# esp_v2.net
KiCad netlist of a schematic drawn in EAGLE
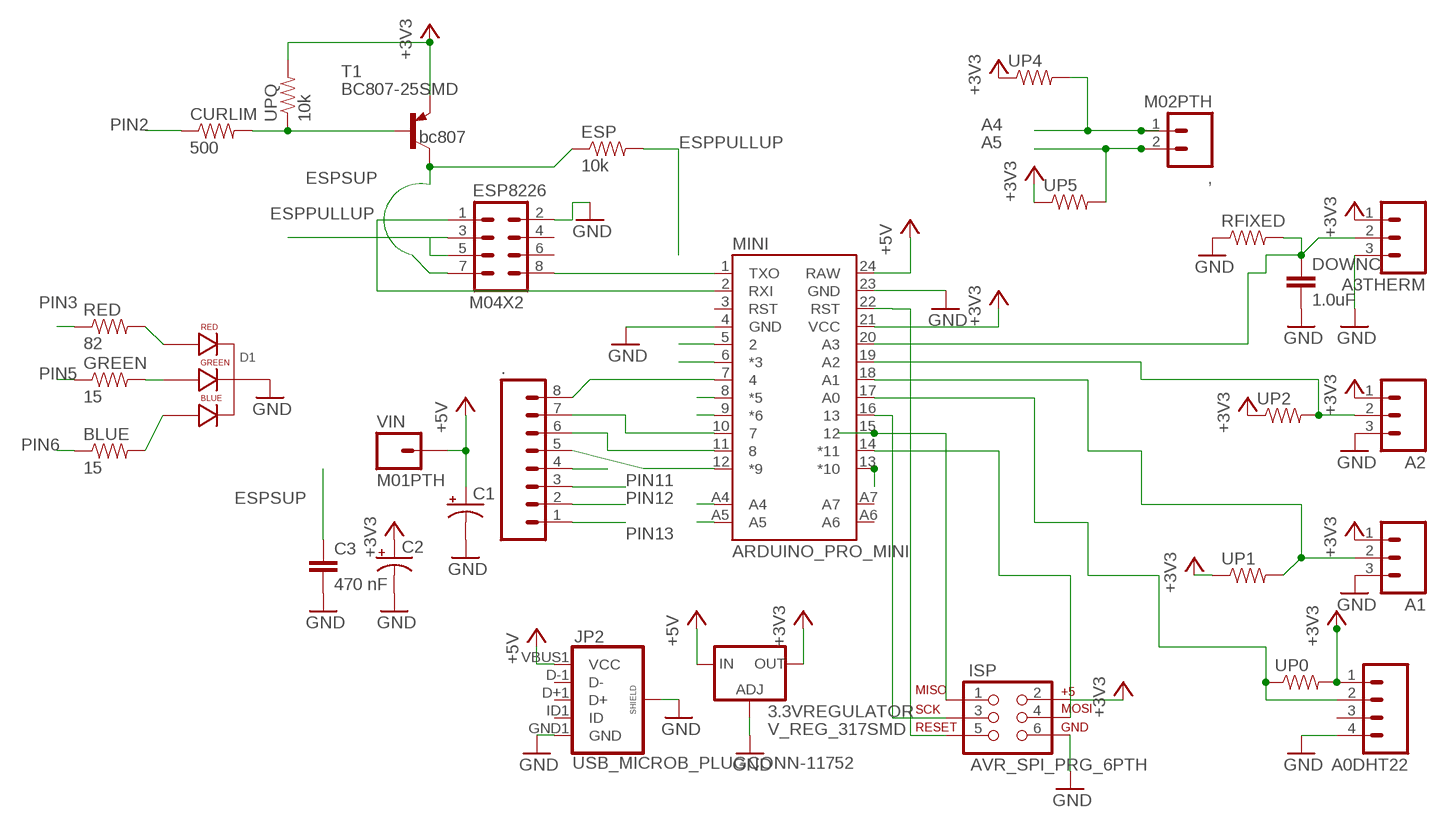
[diagram p0: schematic, sheet 1]

(export (version "E")
  (design (tool "Eeschema 10.0.6"))
  (components
    (comp (ref ",")
      (value "M02PTH")
      (footprint "eagle-import:1X02")
      (libsource (lib "eagle-import") (part "M02PTH"))
    )
    (comp (ref ".")
      (value "M081X08")
      (footprint "eagle-import:1X08")
      (libsource (lib "eagle-import") (part "M081X08"))
    )
    (comp (ref "3.3VREGULATOR")
      (value "V_REG_317SMD")
      (footprint "eagle-import:SOT223")
      (libsource (lib "eagle-import") (part "V_REG_317SMD"))
    )
    (comp (ref "A0DHT22")
      (value "M04PTH")
      (footprint "eagle-import:1X04")
      (libsource (lib "eagle-import") (part "M04PTH"))
    )
    (comp (ref "A1")
      (value "M03PTH")
      (footprint "eagle-import:1X03")
      (libsource (lib "eagle-import") (part "M03PTH"))
    )
    (comp (ref "A2")
      (value "M03PTH")
      (footprint "eagle-import:1X03")
      (libsource (lib "eagle-import") (part "M03PTH"))
    )
    (comp (ref "A3THERM")
      (value "M03PTH")
      (footprint "eagle-import:1X03")
      (libsource (lib "eagle-import") (part "M03PTH"))
    )
    (comp (ref "BLUE")
      (value "15")
      (footprint "eagle-import:0805")
      (libsource (lib "eagle-import") (part "0.3OHM-1/8W-1%(0805)"))
    )
    (comp (ref "C1")
      (value "10UF-25V-20%(PTH)")
      (footprint "eagle-import:CPOL-RADIAL-10UF-25V")
      (libsource (lib "eagle-import") (part "10UF-25V-20%(PTH)"))
    )
    (comp (ref "C2")
      (value "10UF-25V-20%(PTH)")
      (footprint "eagle-import:CPOL-RADIAL-10UF-25V")
      (libsource (lib "eagle-import") (part "10UF-25V-20%(PTH)"))
    )
    (comp (ref "C3")
      (value "470 nF")
      (footprint "eagle-import:0805")
      (libsource (lib "eagle-import") (part "1.0UF-25V-+80/-20(0805)"))
    )
    (comp (ref "CURLIM")
      (value "500")
      (footprint "eagle-import:0805")
      (libsource (lib "eagle-import") (part "0.3OHM-1/8W-1%(0805)"))
    )
    (comp (ref "D1")
      (value "LED-RGB-CC-THRUDIFFUSE")
      (footprint "eagle-import:LED-RGB-THRU")
      (libsource (lib "eagle-import") (part "LED-RGB-CC-THRUDIFFUSE"))
    )
    (comp (ref "DOWNC")
      (value "1.0uF")
      (footprint "eagle-import:0805")
      (libsource (lib "eagle-import") (part "1.0UF-25V-+80/-20(0805)"))
    )
    (comp (ref "ESP")
      (value "10k")
      (footprint "eagle-import:0805")
      (libsource (lib "eagle-import") (part "0.3OHM-1/8W-1%(0805)"))
    )
    (comp (ref "ESP8226")
      (value "M04X2")
      (footprint "eagle-import:2X4")
      (libsource (lib "eagle-import") (part "M04X2"))
    )
    (comp (ref "GREEN")
      (value "15")
      (footprint "eagle-import:0805")
      (libsource (lib "eagle-import") (part "0.3OHM-1/8W-1%(0805)"))
    )
    (comp (ref "ISP")
      (value "AVR_SPI_PRG_6PTH")
      (footprint "eagle-import:2X3")
      (libsource (lib "eagle-import") (part "AVR_SPI_PRG_6PTH"))
    )
    (comp (ref "JP2")
      (value "USB_MICROB_PLUGCONN-11752")
      (footprint "eagle-import:USB-B-MICRO-SMD_V03")
      (libsource (lib "eagle-import") (part "USB_MICROB_PLUGCONN-11752"))
    )
    (comp (ref "MINI")
      (value "ARDUINO_PRO_MINI")
      (footprint "eagle-import:ARDUINO_PRO_MINI")
      (libsource (lib "eagle-import") (part "ARDUINO_PRO_MINI"))
    )
    (comp (ref "RED")
      (value "82")
      (footprint "eagle-import:0805")
      (libsource (lib "eagle-import") (part "0.3OHM-1/8W-1%(0805)"))
    )
    (comp (ref "RFIXED")
      (value "0.3OHM-1/8W-1%(0805)")
      (footprint "eagle-import:0805")
      (libsource (lib "eagle-import") (part "0.3OHM-1/8W-1%(0805)"))
    )
    (comp (ref "T1")
      (value "BC807-25SMD")
      (footprint "eagle-import:SOT23-BEC")
      (libsource (lib "eagle-import") (part "BC807SMD-25"))
    )
    (comp (ref "UP0")
      (value "0.3OHM-1/8W-1%(0805)")
      (footprint "eagle-import:0805")
      (libsource (lib "eagle-import") (part "0.3OHM-1/8W-1%(0805)"))
    )
    (comp (ref "UP1")
      (value "0.3OHM-1/8W-1%(0805)")
      (footprint "eagle-import:0805")
      (libsource (lib "eagle-import") (part "0.3OHM-1/8W-1%(0805)"))
    )
    (comp (ref "UP2")
      (value "0.3OHM-1/8W-1%(0805)")
      (footprint "eagle-import:0805")
      (libsource (lib "eagle-import") (part "0.3OHM-1/8W-1%(0805)"))
    )
    (comp (ref "UP4")
      (value "0.3OHM-1/8W-1%(0805)")
      (footprint "eagle-import:0805")
      (libsource (lib "eagle-import") (part "0.3OHM-1/8W-1%(0805)"))
    )
    (comp (ref "UP5")
      (value "0.3OHM-1/8W-1%(0805)")
      (footprint "eagle-import:0805")
      (libsource (lib "eagle-import") (part "0.3OHM-1/8W-1%(0805)"))
    )
    (comp (ref "UPQ")
      (value "10k")
      (footprint "eagle-import:0805")
      (libsource (lib "eagle-import") (part "0.3OHM-1/8W-1%(0805)"))
    )
    (comp (ref "VIN")
      (value "M01PTH")
      (footprint "eagle-import:1X01")
      (libsource (lib "eagle-import") (part "M01PTH"))
    )
  )
  (nets
    (net (code "1") (name "+3V3") (class "Default")
      (node (ref "3.3VREGULATOR") (pin "2") (pinfunction "OUT_2") (pintype "output"))
      (node (ref "A0DHT22") (pin "1") (pinfunction "1_1") (pintype "passive"))
      (node (ref "A1") (pin "1") (pinfunction "1_1") (pintype "passive"))
      (node (ref "A2") (pin "1") (pinfunction "1_1") (pintype "passive"))
      (node (ref "A3THERM") (pin "1") (pinfunction "1_1") (pintype "passive"))
      (node (ref "C2") (pin "1") (pinfunction "+_1") (pintype "passive"))
      (node (ref "ISP") (pin "2") (pinfunction "2_2") (pintype "passive"))
      (node (ref "MINI") (pin "21") (pinfunction "VCC_21") (pintype "bidirectional"))
      (node (ref "T1") (pin "E") (pinfunction "E_E") (pintype "passive"))
      (node (ref "UP0") (pin "2") (pinfunction "2_2") (pintype "passive"))
      (node (ref "UP1") (pin "1") (pinfunction "1_1") (pintype "passive"))
      (node (ref "UP2") (pin "1") (pinfunction "1_1") (pintype "passive"))
      (node (ref "UP4") (pin "1") (pinfunction "1_1") (pintype "passive"))
      (node (ref "UP5") (pin "1") (pinfunction "1_1") (pintype "passive"))
      (node (ref "UPQ") (pin "2") (pinfunction "2_2") (pintype "passive"))
    )
    (net (code "2") (name "+5V") (class "Default")
      (node (ref "3.3VREGULATOR") (pin "3") (pinfunction "IN_3") (pintype "input"))
      (node (ref "C1") (pin "1") (pinfunction "+_1") (pintype "passive"))
      (node (ref "JP2") (pin "VBUS1") (pinfunction "VCC_VBUS1") (pintype "bidirectional"))
      (node (ref "MINI") (pin "24") (pinfunction "RAW_24") (pintype "bidirectional"))
      (node (ref "VIN") (pin "1") (pinfunction "1_1") (pintype "passive"))
    )
    (net (code "3") (name "/A4") (class "Default")
      (node (ref ",") (pin "1") (pinfunction "1_1") (pintype "passive"))
      (node (ref "MINI") (pin "A4") (pinfunction "A4_A4") (pintype "bidirectional"))
      (node (ref "UP4") (pin "2") (pinfunction "2_2") (pintype "passive"))
    )
    (net (code "4") (name "/A5") (class "Default")
      (node (ref ",") (pin "2") (pinfunction "2_2") (pintype "passive"))
      (node (ref "MINI") (pin "A5") (pinfunction "A5_A5") (pintype "bidirectional"))
      (node (ref "UP5") (pin "2") (pinfunction "2_2") (pintype "passive"))
    )
    (net (code "5") (name "/ESPPULLUP") (class "Default")
      (node (ref "ESP") (pin "2") (pinfunction "2_2") (pintype "passive"))
      (node (ref "ESP8226") (pin "3") (pinfunction "3_3") (pintype "passive"))
      (node (ref "ESP8226") (pin "5") (pinfunction "5_5") (pintype "passive"))
    )
    (net (code "6") (name "/ESPSUP") (class "Default")
      (node (ref "C3") (pin "1") (pinfunction "1_1") (pintype "passive"))
      (node (ref "ESP") (pin "1") (pinfunction "1_1") (pintype "passive"))
      (node (ref "ESP8226") (pin "7") (pinfunction "7_7") (pintype "passive"))
      (node (ref "T1") (pin "C") (pinfunction "C_C") (pintype "passive"))
    )
    (net (code "7") (name "/PIN2") (class "Default")
      (node (ref "CURLIM") (pin "1") (pinfunction "1_1") (pintype "passive"))
      (node (ref "MINI") (pin "5") (pinfunction "2_5") (pintype "bidirectional"))
    )
    (net (code "8") (name "/PIN3") (class "Default")
      (node (ref "MINI") (pin "6") (pinfunction "*3_6") (pintype "bidirectional"))
      (node (ref "RED") (pin "1") (pinfunction "1_1") (pintype "passive"))
    )
    (net (code "9") (name "/PIN5") (class "Default")
      (node (ref "GREEN") (pin "1") (pinfunction "1_1") (pintype "passive"))
      (node (ref "MINI") (pin "8") (pinfunction "*5_8") (pintype "bidirectional"))
    )
    (net (code "10") (name "/PIN6") (class "Default")
      (node (ref "BLUE") (pin "1") (pinfunction "1_1") (pintype "passive"))
      (node (ref "MINI") (pin "9") (pinfunction "*6_9") (pintype "bidirectional"))
    )
    (net (code "11") (name "/PIN10") (class "Default")
      (node (ref ".") (pin "4") (pinfunction "4_4") (pintype "passive"))
      (node (ref "MINI") (pin "13") (pinfunction "*10_13") (pintype "bidirectional"))
    )
    (net (code "12") (name "/PIN11") (class "Default")
      (node (ref ".") (pin "3") (pinfunction "3_3") (pintype "passive"))
      (node (ref "ISP") (pin "4") (pinfunction "4_4") (pintype "passive"))
      (node (ref "MINI") (pin "14") (pinfunction "*11_14") (pintype "bidirectional"))
    )
    (net (code "13") (name "/PIN12") (class "Default")
      (node (ref ".") (pin "2") (pinfunction "2_2") (pintype "passive"))
      (node (ref "ISP") (pin "1") (pinfunction "1_1") (pintype "passive"))
      (node (ref "MINI") (pin "15") (pinfunction "12_15") (pintype "bidirectional"))
    )
    (net (code "14") (name "/PIN13") (class "Default")
      (node (ref ".") (pin "1") (pinfunction "1_1") (pintype "passive"))
      (node (ref "ISP") (pin "3") (pinfunction "3_3") (pintype "passive"))
      (node (ref "MINI") (pin "16") (pinfunction "13_16") (pintype "bidirectional"))
    )
    (net (code "15") (name "GND") (class "Default")
      (node (ref "3.3VREGULATOR") (pin "1") (pinfunction "ADJ_1") (pintype "input"))
      (node (ref "A0DHT22") (pin "4") (pinfunction "4_4") (pintype "passive"))
      (node (ref "A1") (pin "3") (pinfunction "3_3") (pintype "passive"))
      (node (ref "A2") (pin "3") (pinfunction "3_3") (pintype "passive"))
      (node (ref "A3THERM") (pin "3") (pinfunction "3_3") (pintype "passive"))
      (node (ref "C1") (pin "2") (pinfunction "-_2") (pintype "passive"))
      (node (ref "C2") (pin "2") (pinfunction "-_2") (pintype "passive"))
      (node (ref "C3") (pin "2") (pinfunction "2_2") (pintype "passive"))
      (node (ref "D1") (pin "2") (pinfunction "CATHODE_2") (pintype "bidirectional"))
      (node (ref "DOWNC") (pin "2") (pinfunction "2_2") (pintype "passive"))
      (node (ref "ESP8226") (pin "2") (pinfunction "2_2") (pintype "passive"))
      (node (ref "ISP") (pin "6") (pinfunction "6_6") (pintype "passive"))
      (node (ref "JP2") (pin "GND1") (pinfunction "GND_GND1") (pintype "bidirectional"))
      (node (ref "JP2") (pin "SHIELD1") (pinfunction "SHIELD_SHIELD1") (pintype "bidirectional"))
      (node (ref "JP2") (pin "SHIELD2") (pinfunction "SHIELD_SHIELD2") (pintype "bidirectional"))
      (node (ref "JP2") (pin "SHIELD3") (pinfunction "SHIELD_SHIELD3") (pintype "bidirectional"))
      (node (ref "MINI") (pin "23") (pinfunction "GND_23") (pintype "bidirectional"))
      (node (ref "MINI") (pin "4") (pinfunction "GND_4") (pintype "bidirectional"))
      (node (ref "RFIXED") (pin "1") (pinfunction "1_1") (pintype "passive"))
    )
    (net (code "16") (name "Net-(CURLIM-Pad2)") (class "Default")
      (node (ref "CURLIM") (pin "2") (pinfunction "2_2") (pintype "passive"))
      (node (ref "T1") (pin "B") (pinfunction "B_B") (pintype "passive"))
      (node (ref "UPQ") (pin "1") (pinfunction "1_1") (pintype "passive"))
    )
    (net (code "17") (name "Net-(D1-BLUE_CATHODE)") (class "Default")
      (node (ref "BLUE") (pin "2") (pinfunction "2_2") (pintype "passive"))
      (node (ref "D1") (pin "4") (pinfunction "BLUE_CATHODE_4") (pintype "bidirectional"))
    )
    (net (code "18") (name "Net-(D1-GREEN_CATHODE)") (class "Default")
      (node (ref "D1") (pin "3") (pinfunction "GREEN_CATHODE_3") (pintype "bidirectional"))
      (node (ref "GREEN") (pin "2") (pinfunction "2_2") (pintype "passive"))
    )
    (net (code "19") (name "Net-(D1-RED_CATHODE)") (class "Default")
      (node (ref "D1") (pin "1") (pinfunction "RED_CATHODE_1") (pintype "bidirectional"))
      (node (ref "RED") (pin "2") (pinfunction "2_2") (pintype "passive"))
    )
    (net (code "20") (name "Net-(ISP-Pad5)") (class "Default")
      (node (ref "ISP") (pin "5") (pinfunction "5_5") (pintype "passive"))
      (node (ref "MINI") (pin "22") (pinfunction "RST_22") (pintype "bidirectional"))
    )
    (net (code "21") (name "Net-(MINI-*9)") (class "Default")
      (node (ref ".") (pin "5") (pinfunction "5_5") (pintype "passive"))
      (node (ref "MINI") (pin "12") (pinfunction "*9_12") (pintype "bidirectional"))
    )
    (net (code "22") (name "Net-(MINI-4)") (class "Default")
      (node (ref ".") (pin "8") (pinfunction "8_8") (pintype "passive"))
      (node (ref "MINI") (pin "7") (pinfunction "4_7") (pintype "bidirectional"))
    )
    (net (code "23") (name "Net-(MINI-7)") (class "Default")
      (node (ref ".") (pin "7") (pinfunction "7_7") (pintype "passive"))
      (node (ref "MINI") (pin "10") (pinfunction "7_10") (pintype "bidirectional"))
    )
    (net (code "24") (name "Net-(MINI-8)") (class "Default")
      (node (ref ".") (pin "6") (pinfunction "6_6") (pintype "passive"))
      (node (ref "MINI") (pin "11") (pinfunction "8_11") (pintype "bidirectional"))
    )
    (net (code "25") (name "Net-(MINI-A0)") (class "Default")
      (node (ref "A0DHT22") (pin "2") (pinfunction "2_2") (pintype "passive"))
      (node (ref "MINI") (pin "17") (pinfunction "A0_17") (pintype "bidirectional"))
      (node (ref "UP0") (pin "1") (pinfunction "1_1") (pintype "passive"))
    )
    (net (code "26") (name "Net-(MINI-A1)") (class "Default")
      (node (ref "A1") (pin "2") (pinfunction "2_2") (pintype "passive"))
      (node (ref "MINI") (pin "18") (pinfunction "A1_18") (pintype "bidirectional"))
      (node (ref "UP1") (pin "2") (pinfunction "2_2") (pintype "passive"))
    )
    (net (code "27") (name "Net-(MINI-A2)") (class "Default")
      (node (ref "A2") (pin "2") (pinfunction "2_2") (pintype "passive"))
      (node (ref "MINI") (pin "19") (pinfunction "A2_19") (pintype "bidirectional"))
      (node (ref "UP2") (pin "2") (pinfunction "2_2") (pintype "passive"))
    )
    (net (code "28") (name "Net-(MINI-A3)") (class "Default")
      (node (ref "A3THERM") (pin "2") (pinfunction "2_2") (pintype "passive"))
      (node (ref "DOWNC") (pin "1") (pinfunction "1_1") (pintype "passive"))
      (node (ref "MINI") (pin "20") (pinfunction "A3_20") (pintype "bidirectional"))
      (node (ref "RFIXED") (pin "2") (pinfunction "2_2") (pintype "passive"))
    )
    (net (code "29") (name "Net-(MINI-RXI)") (class "Default")
      (node (ref "ESP8226") (pin "1") (pinfunction "1_1") (pintype "passive"))
      (node (ref "MINI") (pin "2") (pinfunction "RXI_2") (pintype "bidirectional"))
    )
    (net (code "30") (name "Net-(MINI-TXO)") (class "Default")
      (node (ref "ESP8226") (pin "8") (pinfunction "8_8") (pintype "passive"))
      (node (ref "MINI") (pin "1") (pinfunction "TXO_1") (pintype "bidirectional"))
    )
    (net (code "31") (name "unconnected-(A0DHT22-Pad3)") (class "Default")
      (node (ref "A0DHT22") (pin "3") (pinfunction "3_3") (pintype "passive"))
    )
    (net (code "32") (name "unconnected-(ESP8226-Pad4)") (class "Default")
      (node (ref "ESP8226") (pin "4") (pinfunction "4_4") (pintype "passive"))
    )
    (net (code "33") (name "unconnected-(ESP8226-Pad6)") (class "Default")
      (node (ref "ESP8226") (pin "6") (pinfunction "6_6") (pintype "passive"))
    )
    (net (code "34") (name "unconnected-(JP2-D+-PadD+1)") (class "Default")
      (node (ref "JP2") (pin "D+1") (pinfunction "D+_D+1") (pintype "bidirectional"))
    )
    (net (code "35") (name "unconnected-(JP2-D--PadD-1)") (class "Default")
      (node (ref "JP2") (pin "D-1") (pinfunction "D-_D-1") (pintype "bidirectional"))
    )
    (net (code "36") (name "unconnected-(JP2-ID-PadID1)") (class "Default")
      (node (ref "JP2") (pin "ID1") (pinfunction "ID_ID1") (pintype "bidirectional"))
    )
    (net (code "37") (name "unconnected-(MINI-PadA6)") (class "Default")
      (node (ref "MINI") (pin "A6") (pinfunction "A6_A6") (pintype "bidirectional"))
    )
    (net (code "38") (name "unconnected-(MINI-PadA7)") (class "Default")
      (node (ref "MINI") (pin "A7") (pinfunction "A7_A7") (pintype "bidirectional"))
    )
    (net (code "39") (name "unconnected-(MINI-RST-Pad3)") (class "Default")
      (node (ref "MINI") (pin "3") (pinfunction "RST_3") (pintype "bidirectional"))
    )
  )
)
